# fesz_boundary_value_meter.net
KiCad netlist of a schematic drawn in EAGLE
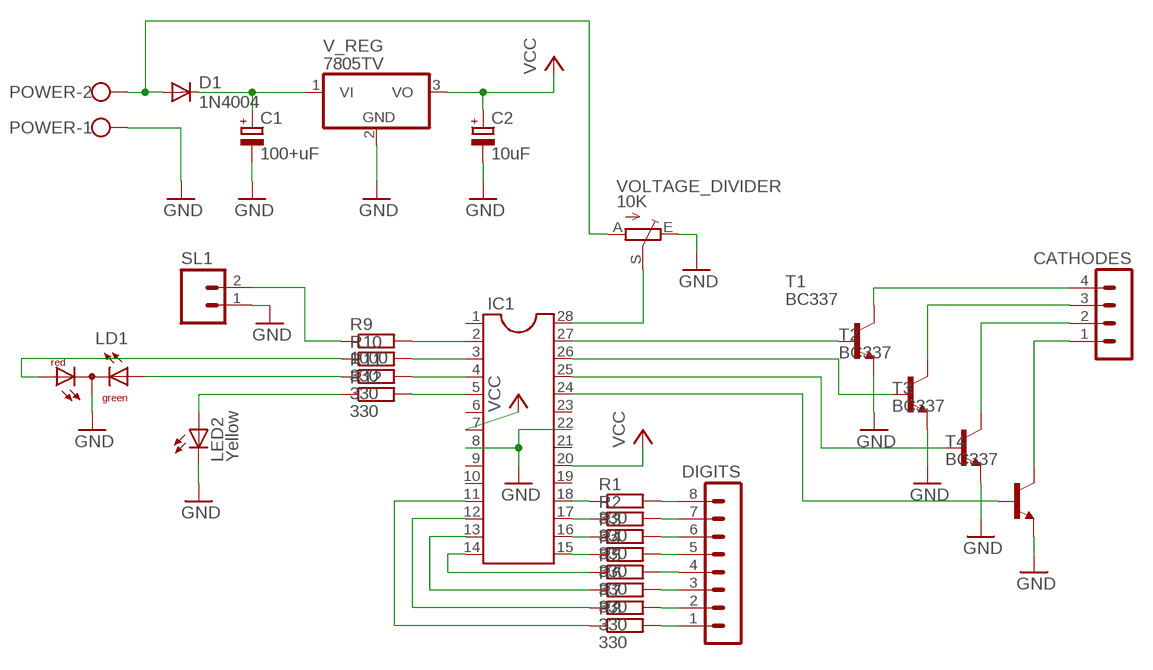
[diagram p0: schematic, sheet 1]

(export (version "E")
  (design (tool "Eeschema 10.0.6"))
  (components
    (comp (ref "C1")
      (value "100+uF")
      (footprint "eagle-import:E2,5-6")
      (libsource (lib "eagle-import") (part "CPOL-EUE2.5-6"))
    )
    (comp (ref "C2")
      (value "10uF")
      (footprint "eagle-import:E2,5-6E")
      (libsource (lib "eagle-import") (part "CPOL-EUE2,5-6E"))
    )
    (comp (ref "CATHODES")
      (value "MA04-1")
      (footprint "eagle-import:MA04-1")
      (libsource (lib "eagle-import") (part "MA04-1"))
    )
    (comp (ref "D1")
      (value "1N4004")
      (footprint "eagle-import:DO41-10")
      (libsource (lib "eagle-import") (part "1N4004"))
    )
    (comp (ref "DIGITS")
      (value "MA08-1")
      (footprint "eagle-import:MA08-1")
      (libsource (lib "eagle-import") (part "MA08-1"))
    )
    (comp (ref "IC1")
      (value "DIL28-3")
      (footprint "eagle-import:DIL28-3")
      (libsource (lib "eagle-import") (part "DIL28-3"))
    )
    (comp (ref "LD1")
      (value "DUOLED-RG-C")
      (footprint "eagle-import:DUOLED-C-5MM")
      (libsource (lib "eagle-import") (part "DUOLED-RG-C"))
    )
    (comp (ref "LED2")
      (value "Yellow")
      (footprint "eagle-import:LED3MM")
      (libsource (lib "eagle-import") (part "LED3MM"))
    )
    (comp (ref "POWER")
      (value "W237-102")
      (footprint "eagle-import:W237-102")
      (fields (field (name "MPN") "237-102"))
      (libsource (lib "eagle-import") (part "W237-102"))
    )
    (comp (ref "R1")
      (value "330")
      (footprint "eagle-import:0207_10")
      (libsource (lib "eagle-import") (part "R-EU_0207/10"))
    )
    (comp (ref "R2")
      (value "330")
      (footprint "eagle-import:0207_10")
      (libsource (lib "eagle-import") (part "R-EU_0207/10"))
    )
    (comp (ref "R3")
      (value "330")
      (footprint "eagle-import:0207_10")
      (libsource (lib "eagle-import") (part "R-EU_0207/10"))
    )
    (comp (ref "R4")
      (value "330")
      (footprint "eagle-import:0207_10")
      (libsource (lib "eagle-import") (part "R-EU_0207/10"))
    )
    (comp (ref "R5")
      (value "330")
      (footprint "eagle-import:0207_10")
      (libsource (lib "eagle-import") (part "R-EU_0207/10"))
    )
    (comp (ref "R6")
      (value "330")
      (footprint "eagle-import:0207_10")
      (libsource (lib "eagle-import") (part "R-EU_0207/10"))
    )
    (comp (ref "R7")
      (value "330")
      (footprint "eagle-import:0207_10")
      (libsource (lib "eagle-import") (part "R-EU_0207/10"))
    )
    (comp (ref "R8")
      (value "330")
      (footprint "eagle-import:0207_10")
      (libsource (lib "eagle-import") (part "R-EU_0207/10"))
    )
    (comp (ref "R9")
      (value "1000")
      (footprint "eagle-import:0207_10")
      (libsource (lib "eagle-import") (part "R-EU_0207/10"))
    )
    (comp (ref "R10")
      (value "330")
      (footprint "eagle-import:0207_10")
      (libsource (lib "eagle-import") (part "R-EU_0207/10"))
    )
    (comp (ref "R11")
      (value "330")
      (footprint "eagle-import:0207_10")
      (libsource (lib "eagle-import") (part "R-EU_0207/10"))
    )
    (comp (ref "R12")
      (value "330")
      (footprint "eagle-import:0207_10")
      (libsource (lib "eagle-import") (part "R-EU_0207/10"))
    )
    (comp (ref "SL1")
      (value "MA02")
      (footprint "eagle-import:02PA")
      (libsource (lib "eagle-import") (part "MA02"))
    )
    (comp (ref "T1")
      (value "BC337")
      (footprint "eagle-import:TO92")
      (libsource (lib "eagle-import") (part "BC337"))
    )
    (comp (ref "T2")
      (value "BC337")
      (footprint "eagle-import:TO92")
      (libsource (lib "eagle-import") (part "BC337"))
    )
    (comp (ref "T3")
      (value "BC337")
      (footprint "eagle-import:TO92")
      (libsource (lib "eagle-import") (part "BC337"))
    )
    (comp (ref "T4")
      (value "BC337")
      (footprint "eagle-import:TO92")
      (libsource (lib "eagle-import") (part "BC337"))
    )
    (comp (ref "VOLTAGE_DIVIDER")
      (value "10K")
      (footprint "eagle-import:S64W")
      (libsource (lib "eagle-import") (part "TRIM_EU-S64W"))
    )
    (comp (ref "V_REG")
      (value "7805TV")
      (footprint "eagle-import:TO220V")
      (libsource (lib "eagle-import") (part "78TV05"))
    )
  )
  (nets
    (net (code "1") (name "GND") (class "Default")
      (node (ref "C1") (pin "-") (pinfunction "-_-") (pintype "passive"))
      (node (ref "C2") (pin "-") (pinfunction "-_-") (pintype "passive"))
      (node (ref "IC1") (pin "22") (pinfunction "22_22") (pintype "passive"))
      (node (ref "IC1") (pin "8") (pinfunction "8_8") (pintype "passive"))
      (node (ref "LD1") (pin "C") (pinfunction "C_C") (pintype "passive"))
      (node (ref "LED2") (pin "K") (pinfunction "C_K") (pintype "passive"))
      (node (ref "POWER") (pin "1") (pinfunction "KL_1") (pintype "passive"))
      (node (ref "SL1") (pin "1") (pinfunction "1_1") (pintype "passive"))
      (node (ref "T1") (pin "1") (pinfunction "E_1") (pintype "passive"))
      (node (ref "T2") (pin "1") (pinfunction "E_1") (pintype "passive"))
      (node (ref "T3") (pin "1") (pinfunction "E_1") (pintype "passive"))
      (node (ref "T4") (pin "1") (pinfunction "E_1") (pintype "passive"))
      (node (ref "VOLTAGE_DIVIDER") (pin "E") (pinfunction "E_E") (pintype "passive"))
      (node (ref "V_REG") (pin "2") (pinfunction "GND_2") (pintype "passive"))
    )
    (net (code "2") (name "Net-(DIGITS-Pad1)") (class "Default")
      (node (ref "DIGITS") (pin "1") (pinfunction "1_1") (pintype "passive"))
      (node (ref "R8") (pin "2") (pinfunction "2_2") (pintype "passive"))
    )
    (net (code "3") (name "Net-(DIGITS-Pad2)") (class "Default")
      (node (ref "DIGITS") (pin "2") (pinfunction "2_2") (pintype "passive"))
      (node (ref "R7") (pin "2") (pinfunction "2_2") (pintype "passive"))
    )
    (net (code "4") (name "Net-(DIGITS-Pad3)") (class "Default")
      (node (ref "DIGITS") (pin "3") (pinfunction "3_3") (pintype "passive"))
      (node (ref "R6") (pin "2") (pinfunction "2_2") (pintype "passive"))
    )
    (net (code "5") (name "Net-(DIGITS-Pad4)") (class "Default")
      (node (ref "DIGITS") (pin "4") (pinfunction "4_4") (pintype "passive"))
      (node (ref "R5") (pin "2") (pinfunction "2_2") (pintype "passive"))
    )
    (net (code "6") (name "Net-(DIGITS-Pad5)") (class "Default")
      (node (ref "DIGITS") (pin "5") (pinfunction "5_5") (pintype "passive"))
      (node (ref "R4") (pin "2") (pinfunction "2_2") (pintype "passive"))
    )
    (net (code "7") (name "Net-(DIGITS-Pad6)") (class "Default")
      (node (ref "DIGITS") (pin "6") (pinfunction "6_6") (pintype "passive"))
      (node (ref "R3") (pin "2") (pinfunction "2_2") (pintype "passive"))
    )
    (net (code "8") (name "Net-(DIGITS-Pad7)") (class "Default")
      (node (ref "DIGITS") (pin "7") (pinfunction "7_7") (pintype "passive"))
      (node (ref "R2") (pin "2") (pinfunction "2_2") (pintype "passive"))
    )
    (net (code "9") (name "Net-(DIGITS-Pad8)") (class "Default")
      (node (ref "DIGITS") (pin "8") (pinfunction "8_8") (pintype "passive"))
      (node (ref "R1") (pin "2") (pinfunction "2_2") (pintype "passive"))
    )
    (net (code "10") (name "Net-(IC1-Pad2)") (class "Default")
      (node (ref "IC1") (pin "2") (pinfunction "2_2") (pintype "passive"))
      (node (ref "R9") (pin "2") (pinfunction "2_2") (pintype "passive"))
    )
    (net (code "11") (name "Net-(IC1-Pad3)") (class "Default")
      (node (ref "IC1") (pin "3") (pinfunction "3_3") (pintype "passive"))
      (node (ref "R10") (pin "2") (pinfunction "2_2") (pintype "passive"))
    )
    (net (code "12") (name "Net-(IC1-Pad4)") (class "Default")
      (node (ref "IC1") (pin "4") (pinfunction "4_4") (pintype "passive"))
      (node (ref "R11") (pin "2") (pinfunction "2_2") (pintype "passive"))
    )
    (net (code "13") (name "Net-(IC1-Pad5)") (class "Default")
      (node (ref "IC1") (pin "5") (pinfunction "5_5") (pintype "passive"))
      (node (ref "R12") (pin "2") (pinfunction "2_2") (pintype "passive"))
    )
    (net (code "14") (name "Net-(IC1-Pad11)") (class "Default")
      (node (ref "IC1") (pin "11") (pinfunction "11_11") (pintype "passive"))
      (node (ref "R8") (pin "1") (pinfunction "1_1") (pintype "passive"))
    )
    (net (code "15") (name "Net-(IC1-Pad12)") (class "Default")
      (node (ref "IC1") (pin "12") (pinfunction "12_12") (pintype "passive"))
      (node (ref "R7") (pin "1") (pinfunction "1_1") (pintype "passive"))
    )
    (net (code "16") (name "Net-(IC1-Pad13)") (class "Default")
      (node (ref "IC1") (pin "13") (pinfunction "13_13") (pintype "passive"))
      (node (ref "R6") (pin "1") (pinfunction "1_1") (pintype "passive"))
    )
    (net (code "17") (name "Net-(IC1-Pad14)") (class "Default")
      (node (ref "IC1") (pin "14") (pinfunction "14_14") (pintype "passive"))
      (node (ref "R5") (pin "1") (pinfunction "1_1") (pintype "passive"))
    )
    (net (code "18") (name "Net-(IC1-Pad15)") (class "Default")
      (node (ref "IC1") (pin "15") (pinfunction "15_15") (pintype "passive"))
      (node (ref "R4") (pin "1") (pinfunction "1_1") (pintype "passive"))
    )
    (net (code "19") (name "Net-(IC1-Pad16)") (class "Default")
      (node (ref "IC1") (pin "16") (pinfunction "16_16") (pintype "passive"))
      (node (ref "R3") (pin "1") (pinfunction "1_1") (pintype "passive"))
    )
    (net (code "20") (name "Net-(IC1-Pad17)") (class "Default")
      (node (ref "IC1") (pin "17") (pinfunction "17_17") (pintype "passive"))
      (node (ref "R2") (pin "1") (pinfunction "1_1") (pintype "passive"))
    )
    (net (code "21") (name "Net-(IC1-Pad18)") (class "Default")
      (node (ref "IC1") (pin "18") (pinfunction "18_18") (pintype "passive"))
      (node (ref "R1") (pin "1") (pinfunction "1_1") (pintype "passive"))
    )
    (net (code "22") (name "Net-(IC1-Pad28)") (class "Default")
      (node (ref "IC1") (pin "28") (pinfunction "28_28") (pintype "passive"))
      (node (ref "VOLTAGE_DIVIDER") (pin "S") (pinfunction "S_S") (pintype "passive"))
    )
    (net (code "23") (name "Net-(LD1-AG)") (class "Default")
      (node (ref "LD1") (pin "AX") (pinfunction "AG_AX") (pintype "passive"))
      (node (ref "R11") (pin "1") (pinfunction "1_1") (pintype "passive"))
    )
    (net (code "24") (name "Net-(LD1-PadAR)") (class "Default")
      (node (ref "LD1") (pin "AR") (pinfunction "AR_AR") (pintype "passive"))
      (node (ref "R10") (pin "1") (pinfunction "1_1") (pintype "passive"))
    )
    (net (code "25") (name "Net-(LED2-PadA)") (class "Default")
      (node (ref "LED2") (pin "A") (pinfunction "A_A") (pintype "passive"))
      (node (ref "R12") (pin "1") (pinfunction "1_1") (pintype "passive"))
    )
    (net (code "26") (name "Net-(POWERB-KL)") (class "Default")
      (node (ref "D1") (pin "A") (pinfunction "A_A") (pintype "passive"))
      (node (ref "POWER") (pin "2") (pinfunction "KL_2") (pintype "passive"))
      (node (ref "VOLTAGE_DIVIDER") (pin "A") (pinfunction "A_A") (pintype "passive"))
    )
    (net (code "27") (name "Net-(R9-Pad1)") (class "Default")
      (node (ref "R9") (pin "1") (pinfunction "1_1") (pintype "passive"))
      (node (ref "SL1") (pin "2") (pinfunction "2_2") (pintype "passive"))
    )
    (net (code "28") (name "Net-(T1-B)") (class "Default")
      (node (ref "IC1") (pin "27") (pinfunction "27_27") (pintype "passive"))
      (node (ref "T1") (pin "2") (pinfunction "B_2") (pintype "passive"))
    )
    (net (code "29") (name "Net-(T1-C)") (class "Default")
      (node (ref "CATHODES") (pin "4") (pinfunction "4_4") (pintype "passive"))
      (node (ref "T1") (pin "3") (pinfunction "C_3") (pintype "passive"))
    )
    (net (code "30") (name "Net-(T2-B)") (class "Default")
      (node (ref "IC1") (pin "26") (pinfunction "26_26") (pintype "passive"))
      (node (ref "T2") (pin "2") (pinfunction "B_2") (pintype "passive"))
    )
    (net (code "31") (name "Net-(T2-C)") (class "Default")
      (node (ref "CATHODES") (pin "3") (pinfunction "3_3") (pintype "passive"))
      (node (ref "T2") (pin "3") (pinfunction "C_3") (pintype "passive"))
    )
    (net (code "32") (name "Net-(T3-B)") (class "Default")
      (node (ref "IC1") (pin "25") (pinfunction "25_25") (pintype "passive"))
      (node (ref "T3") (pin "2") (pinfunction "B_2") (pintype "passive"))
    )
    (net (code "33") (name "Net-(T3-C)") (class "Default")
      (node (ref "CATHODES") (pin "2") (pinfunction "2_2") (pintype "passive"))
      (node (ref "T3") (pin "3") (pinfunction "C_3") (pintype "passive"))
    )
    (net (code "34") (name "Net-(T4-B)") (class "Default")
      (node (ref "IC1") (pin "24") (pinfunction "24_24") (pintype "passive"))
      (node (ref "T4") (pin "2") (pinfunction "B_2") (pintype "passive"))
    )
    (net (code "35") (name "Net-(T4-C)") (class "Default")
      (node (ref "CATHODES") (pin "1") (pinfunction "1_1") (pintype "passive"))
      (node (ref "T4") (pin "3") (pinfunction "C_3") (pintype "passive"))
    )
    (net (code "36") (name "Net-(V_REG-VI)") (class "Default")
      (node (ref "C1") (pin "+") (pinfunction "+_+") (pintype "passive"))
      (node (ref "D1") (pin "C") (pinfunction "C_C") (pintype "passive"))
      (node (ref "V_REG") (pin "1") (pinfunction "VI_1") (pintype "input"))
    )
    (net (code "37") (name "VCC") (class "Default")
      (node (ref "C2") (pin "+") (pinfunction "+_+") (pintype "passive"))
      (node (ref "IC1") (pin "20") (pinfunction "20_20") (pintype "passive"))
      (node (ref "IC1") (pin "7") (pinfunction "7_7") (pintype "passive"))
      (node (ref "V_REG") (pin "3") (pinfunction "VO_3") (pintype "passive"))
    )
    (net (code "38") (name "unconnected-(IC1-Pad1)") (class "Default")
      (node (ref "IC1") (pin "1") (pinfunction "1_1") (pintype "passive"))
    )
    (net (code "39") (name "unconnected-(IC1-Pad6)") (class "Default")
      (node (ref "IC1") (pin "6") (pinfunction "6_6") (pintype "passive"))
    )
    (net (code "40") (name "unconnected-(IC1-Pad9)") (class "Default")
      (node (ref "IC1") (pin "9") (pinfunction "9_9") (pintype "passive"))
    )
    (net (code "41") (name "unconnected-(IC1-Pad10)") (class "Default")
      (node (ref "IC1") (pin "10") (pinfunction "10_10") (pintype "passive"))
    )
    (net (code "42") (name "unconnected-(IC1-Pad19)") (class "Default")
      (node (ref "IC1") (pin "19") (pinfunction "19_19") (pintype "passive"))
    )
    (net (code "43") (name "unconnected-(IC1-Pad21)") (class "Default")
      (node (ref "IC1") (pin "21") (pinfunction "21_21") (pintype "passive"))
    )
    (net (code "44") (name "unconnected-(IC1-Pad23)") (class "Default")
      (node (ref "IC1") (pin "23") (pinfunction "23_23") (pintype "passive"))
    )
  )
)
